# batteryBalancer.net
KiCad netlist of a schematic drawn in EAGLE
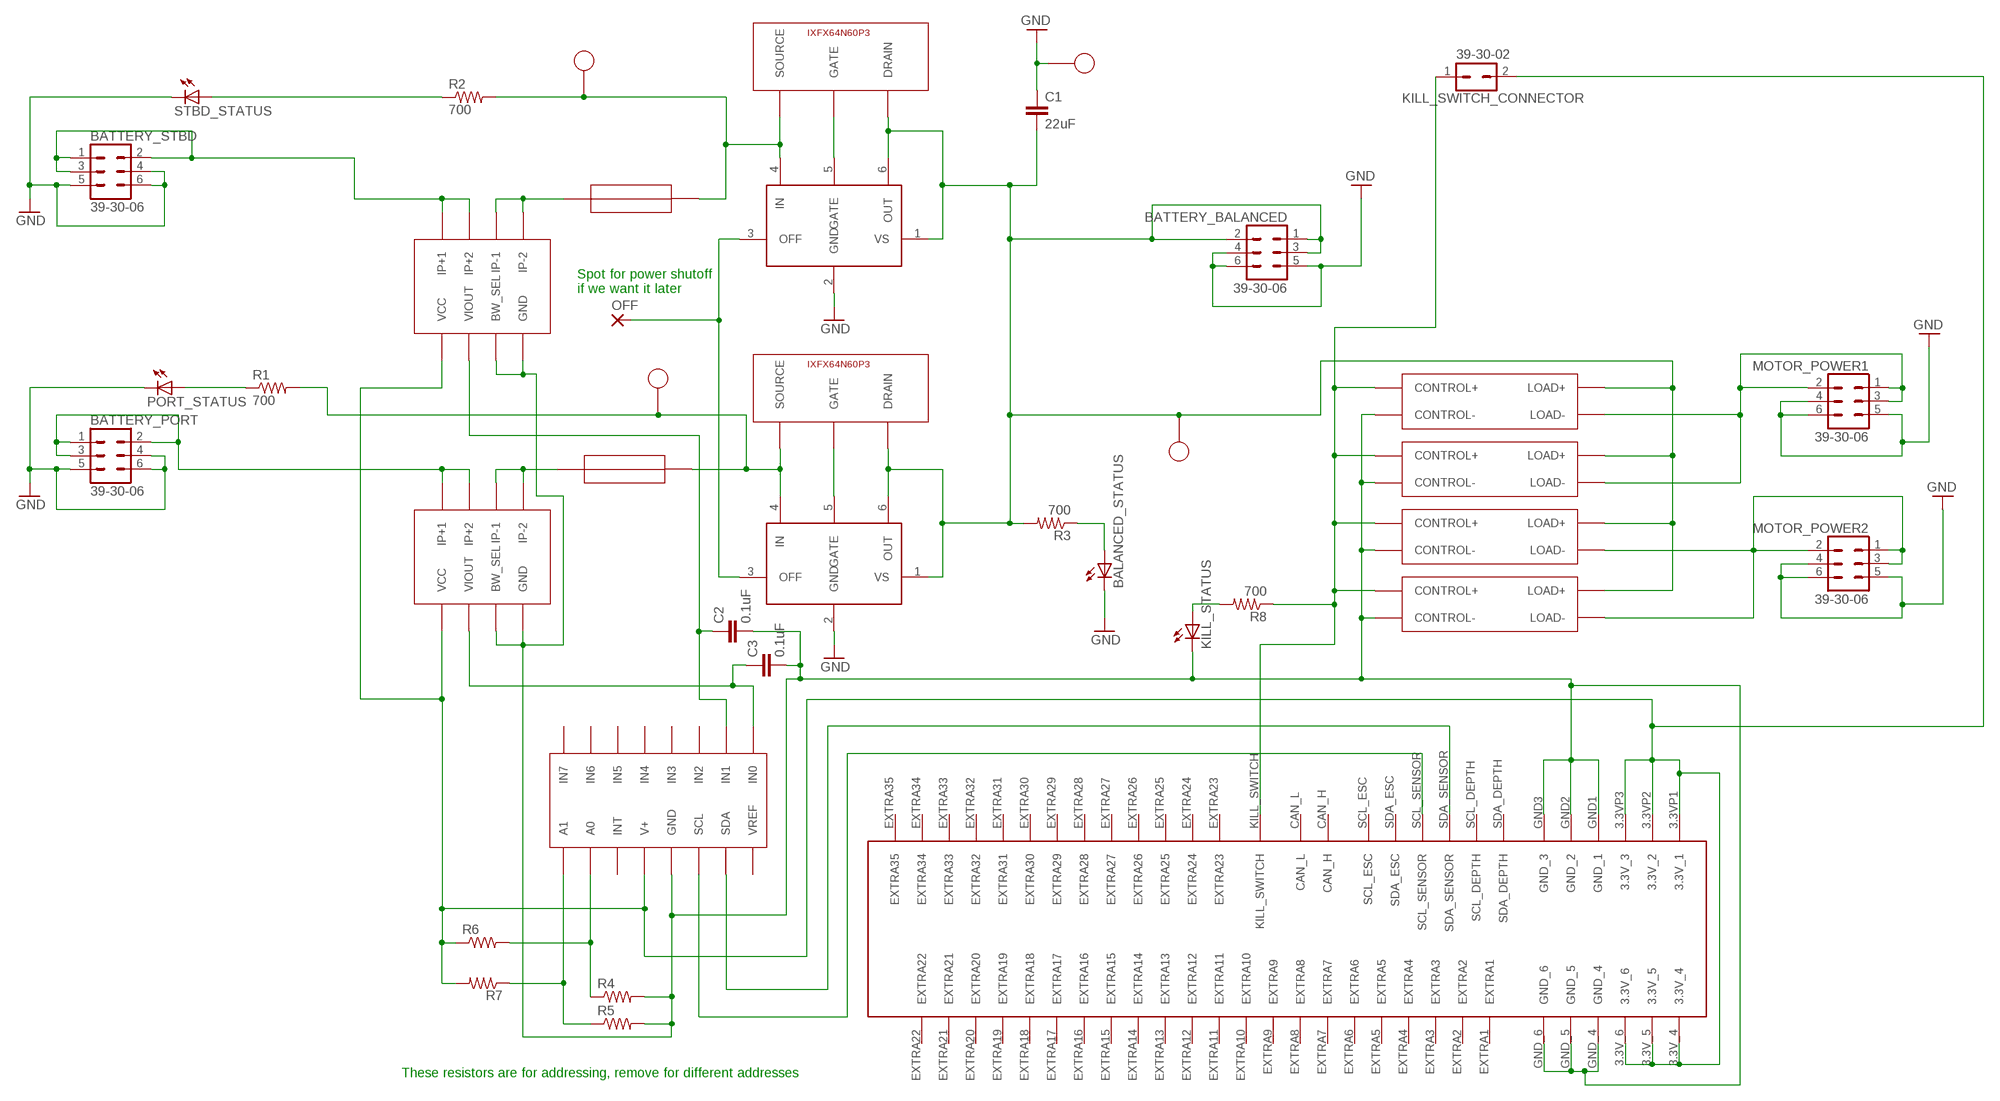
[diagram p0: schematic, sheet 1]

(export (version "E")
  (design (tool "Eeschema 10.0.6"))
  (components
    (comp (ref "ADC")
      (value "ADC128D818")
      (footprint "eagle-import:TSSOP-16")
      (libsource (lib "eagle-import") (part "ADC128D818"))
    )
    (comp (ref "BALANCED_STATUS")
      (value "LTST-S270GKT")
      (footprint "eagle-import:LTST-S270GKT")
      (libsource (lib "eagle-import") (part "LTST-S270GKT"))
    )
    (comp (ref "BATTERY_BALANCED")
      (value "39-30-06")
      (footprint "eagle-import:39-30-_06_")
      (libsource (lib "eagle-import") (part "39-30-?06?"))
    )
    (comp (ref "BATTERY_PORT")
      (value "39-30-06")
      (footprint "eagle-import:39-30-_06_")
      (libsource (lib "eagle-import") (part "39-30-?06?"))
    )
    (comp (ref "BATTERY_STBD")
      (value "39-30-06")
      (footprint "eagle-import:39-30-_06_")
      (libsource (lib "eagle-import") (part "39-30-?06?"))
    )
    (comp (ref "C1")
      (value "22uF")
      (footprint "eagle-import:CAP-PTH-SMALL-KIT")
      (libsource (lib "eagle-import") (part "0.1UF-KIT-EZ-50V-20%"))
    )
    (comp (ref "C2")
      (value "0.1uF")
      (footprint "eagle-import:CAP-PTH-SMALL-KIT")
      (libsource (lib "eagle-import") (part "0.1UF-KIT-EZ-50V-20%"))
    )
    (comp (ref "C3")
      (value "0.1uF")
      (footprint "eagle-import:CAP-PTH-SMALL-KIT")
      (libsource (lib "eagle-import") (part "0.1UF-KIT-EZ-50V-20%"))
    )
    (comp (ref "EDGE_CONNECTOR")
      (value "5530843")
      (footprint "eagle-import:5530843-6-BOARDFINGERS")
      (libsource (lib "eagle-import") (part "5530843"))
    )
    (comp (ref "KILL_STATUS")
      (value "LTST-S270GKT")
      (footprint "eagle-import:LTST-S270GKT")
      (libsource (lib "eagle-import") (part "LTST-S270GKT"))
    )
    (comp (ref "KILL_SWITCH_CONNECTOR")
      (value "39-30-02")
      (footprint "eagle-import:39-30-_02_")
      (libsource (lib "eagle-import") (part "39-30-?02?"))
    )
    (comp (ref "MOTOR_POWER1")
      (value "39-30-06")
      (footprint "eagle-import:39-30-_06_")
      (libsource (lib "eagle-import") (part "39-30-?06?"))
    )
    (comp (ref "MOTOR_POWER2")
      (value "39-30-06")
      (footprint "eagle-import:39-30-_06_")
      (libsource (lib "eagle-import") (part "39-30-?06?"))
    )
    (comp (ref "OFF")
      (value "2,54/1,1")
      (footprint "eagle-import:2,54_1,1")
      (libsource (lib "eagle-import") (part "2,54/1,1"))
    )
    (comp (ref "PORT_CS")
      (value "ACS722")
      (footprint "eagle-import:SOIC-8")
      (libsource (lib "eagle-import") (part "ACS722"))
    )
    (comp (ref "PORT_FC")
      (value "LM5050-1")
      (footprint "eagle-import:SOT23-6")
      (libsource (lib "eagle-import") (part "LM5050-1"))
    )
    (comp (ref "PORT_FET")
      (value "IXFX64N60P3")
      (footprint "eagle-import:IXFX64N60P3")
      (libsource (lib "eagle-import") (part "IXFX64N60P3"))
    )
    (comp (ref "PORT_FUSE")
      (value "01220083Z")
      (footprint "eagle-import:01220083Z")
      (libsource (lib "eagle-import") (part "01220083Z"))
    )
    (comp (ref "PORT_STATUS")
      (value "LTST-S270GKT")
      (footprint "eagle-import:LTST-S270GKT")
      (libsource (lib "eagle-import") (part "LTST-S270GKT"))
    )
    (comp (ref "R1")
      (value "700")
      (footprint "eagle-import:0207_7")
      (libsource (lib "eagle-import") (part "R-US_0207/7"))
    )
    (comp (ref "R2")
      (value "700")
      (footprint "eagle-import:0207_7")
      (libsource (lib "eagle-import") (part "R-US_0207/7"))
    )
    (comp (ref "R3")
      (value "700")
      (footprint "eagle-import:0207_7")
      (libsource (lib "eagle-import") (part "R-US_0207/7"))
    )
    (comp (ref "R4")
      (value "R-US_0204/5")
      (footprint "eagle-import:0204_5")
      (libsource (lib "eagle-import") (part "resistor_348_R-US_0204/5"))
    )
    (comp (ref "R5")
      (value "R-US_0204/5")
      (footprint "eagle-import:0204_5")
      (libsource (lib "eagle-import") (part "resistor_348_R-US_0204/5"))
    )
    (comp (ref "R6")
      (value "R-US_0204/5")
      (footprint "eagle-import:0204_5")
      (libsource (lib "eagle-import") (part "resistor_348_R-US_0204/5"))
    )
    (comp (ref "R7")
      (value "R-US_0204/5")
      (footprint "eagle-import:0204_5")
      (libsource (lib "eagle-import") (part "resistor_348_R-US_0204/5"))
    )
    (comp (ref "R8")
      (value "700")
      (footprint "eagle-import:0207_7")
      (libsource (lib "eagle-import") (part "R-US_0207/7"))
    )
    (comp (ref "RELAY2")
      (value "CMX60D20")
      (footprint "eagle-import:CMX60D20")
      (libsource (lib "eagle-import") (part "CMX60D20"))
    )
    (comp (ref "RELAY3")
      (value "CMX60D20")
      (footprint "eagle-import:CMX60D20")
      (libsource (lib "eagle-import") (part "CMX60D20"))
    )
    (comp (ref "RELAY4")
      (value "CMX60D20")
      (footprint "eagle-import:CMX60D20")
      (libsource (lib "eagle-import") (part "CMX60D20"))
    )
    (comp (ref "RLAY1")
      (value "CMX60D20")
      (footprint "eagle-import:CMX60D20")
      (libsource (lib "eagle-import") (part "CMX60D20"))
    )
    (comp (ref "STBD_CS")
      (value "ACS722")
      (footprint "eagle-import:SOIC-8")
      (libsource (lib "eagle-import") (part "ACS722"))
    )
    (comp (ref "STBD_FC")
      (value "LM5050-1")
      (footprint "eagle-import:SOT23-6")
      (libsource (lib "eagle-import") (part "LM5050-1"))
    )
    (comp (ref "STBD_FET")
      (value "IXFX64N60P3")
      (footprint "eagle-import:IXFX64N60P3")
      (libsource (lib "eagle-import") (part "IXFX64N60P3"))
    )
    (comp (ref "STBD_FUSE")
      (value "01220083Z")
      (footprint "eagle-import:01220083Z")
      (libsource (lib "eagle-import") (part "01220083Z"))
    )
    (comp (ref "STBD_STATUS")
      (value "LTST-S270GKT")
      (footprint "eagle-import:LTST-S270GKT")
      (libsource (lib "eagle-import") (part "LTST-S270GKT"))
    )
    (comp (ref "U$1")
      (value "5010_C")
      (footprint "eagle-import:5010_C")
      (libsource (lib "eagle-import") (part "5010_C"))
    )
    (comp (ref "U$2")
      (value "5010_C")
      (footprint "eagle-import:5010_C")
      (libsource (lib "eagle-import") (part "5010_C"))
    )
    (comp (ref "U$3")
      (value "5010_C")
      (footprint "eagle-import:5010_C")
      (libsource (lib "eagle-import") (part "5010_C"))
    )
    (comp (ref "U$4")
      (value "5010_C")
      (footprint "eagle-import:5010_C")
      (libsource (lib "eagle-import") (part "5010_C"))
    )
  )
  (nets
    (net (code "1") (name "GND") (class "Default")
      (node (ref "BALANCED_STATUS") (pin "CATHODE") (pinfunction "C_CATHODE") (pintype "passive"))
      (node (ref "BATTERY_BALANCED") (pin "4") (pinfunction "4_4") (pintype "passive"))
      (node (ref "BATTERY_BALANCED") (pin "5") (pinfunction "5_5") (pintype "passive"))
      (node (ref "BATTERY_BALANCED") (pin "6") (pinfunction "6_6") (pintype "passive"))
      (node (ref "BATTERY_PORT") (pin "4") (pinfunction "4_4") (pintype "passive"))
      (node (ref "BATTERY_PORT") (pin "5") (pinfunction "5_5") (pintype "passive"))
      (node (ref "BATTERY_PORT") (pin "6") (pinfunction "6_6") (pintype "passive"))
      (node (ref "BATTERY_STBD") (pin "4") (pinfunction "4_4") (pintype "passive"))
      (node (ref "BATTERY_STBD") (pin "5") (pinfunction "5_5") (pintype "passive"))
      (node (ref "BATTERY_STBD") (pin "6") (pinfunction "6_6") (pintype "passive"))
      (node (ref "C1") (pin "1") (pinfunction "1_1") (pintype "passive"))
      (node (ref "MOTOR_POWER1") (pin "4") (pinfunction "4_4") (pintype "passive"))
      (node (ref "MOTOR_POWER1") (pin "5") (pinfunction "5_5") (pintype "passive"))
      (node (ref "MOTOR_POWER1") (pin "6") (pinfunction "6_6") (pintype "passive"))
      (node (ref "MOTOR_POWER2") (pin "4") (pinfunction "4_4") (pintype "passive"))
      (node (ref "MOTOR_POWER2") (pin "5") (pinfunction "5_5") (pintype "passive"))
      (node (ref "MOTOR_POWER2") (pin "6") (pinfunction "6_6") (pintype "passive"))
      (node (ref "PORT_FC") (pin "2") (pinfunction "GND_2") (pintype "bidirectional"))
      (node (ref "PORT_STATUS") (pin "CATHODE") (pinfunction "C_CATHODE") (pintype "passive"))
      (node (ref "STBD_FC") (pin "2") (pinfunction "GND_2") (pintype "bidirectional"))
      (node (ref "STBD_STATUS") (pin "CATHODE") (pinfunction "C_CATHODE") (pintype "passive"))
      (node (ref "U$4") (pin "P$1") (pinfunction "P$1_P$1") (pintype "bidirectional"))
    )
    (net (code "2") (name "Net-(ADC-PadA0)") (class "Default")
      (node (ref "ADC") (pin "A0") (pinfunction "A0_A0") (pintype "bidirectional"))
      (node (ref "R4") (pin "1") (pinfunction "1_1") (pintype "passive"))
      (node (ref "R6") (pin "2") (pinfunction "2_2") (pintype "passive"))
    )
    (net (code "3") (name "Net-(ADC-PadA1)") (class "Default")
      (node (ref "ADC") (pin "A1") (pinfunction "A1_A1") (pintype "bidirectional"))
      (node (ref "R5") (pin "1") (pinfunction "1_1") (pintype "passive"))
      (node (ref "R7") (pin "1") (pinfunction "1_1") (pintype "passive"))
    )
    (net (code "4") (name "Net-(ADC-PadIN0)") (class "Default")
      (node (ref "ADC") (pin "IN0") (pinfunction "IN0_IN0") (pintype "bidirectional"))
      (node (ref "C3") (pin "1") (pinfunction "1_1") (pintype "passive"))
      (node (ref "PORT_CS") (pin "VIOUT") (pinfunction "VIOUT_VIOUT") (pintype "bidirectional"))
    )
    (net (code "5") (name "Net-(ADC-PadIN1)") (class "Default")
      (node (ref "ADC") (pin "IN1") (pinfunction "IN1_IN1") (pintype "bidirectional"))
      (node (ref "C2") (pin "1") (pinfunction "1_1") (pintype "passive"))
      (node (ref "STBD_CS") (pin "VIOUT") (pinfunction "VIOUT_VIOUT") (pintype "bidirectional"))
    )
    (net (code "6") (name "Net-(ADC-PadSCL)") (class "Default")
      (node (ref "ADC") (pin "SCL") (pinfunction "SCL_SCL") (pintype "bidirectional"))
      (node (ref "EDGE_CONNECTOR") (pin "SCL_SENSOR") (pinfunction "SCL_SENSOR_SCL_SENSOR") (pintype "bidirectional"))
    )
    (net (code "7") (name "Net-(ADC-PadSDA)") (class "Default")
      (node (ref "ADC") (pin "SDA") (pinfunction "SDA_SDA") (pintype "bidirectional"))
      (node (ref "EDGE_CONNECTOR") (pin "SDA_SENSOR") (pinfunction "SDA_SENSOR_SDA_SENSOR") (pintype "bidirectional"))
    )
    (net (code "8") (name "Net-(BALANCED_STATUS-A)") (class "Default")
      (node (ref "BALANCED_STATUS") (pin "ANODE") (pinfunction "A_ANODE") (pintype "passive"))
      (node (ref "R3") (pin "1") (pinfunction "1_1") (pintype "passive"))
    )
    (net (code "9") (name "Net-(BATTERY_PORT-Pad1)") (class "Default")
      (node (ref "BATTERY_PORT") (pin "1") (pinfunction "1_1") (pintype "passive"))
      (node (ref "BATTERY_PORT") (pin "2") (pinfunction "2_2") (pintype "passive"))
      (node (ref "BATTERY_PORT") (pin "3") (pinfunction "3_3") (pintype "passive"))
      (node (ref "PORT_CS") (pin "IP+1") (pinfunction "IP+1_IP+1") (pintype "bidirectional"))
      (node (ref "PORT_CS") (pin "IP+2") (pinfunction "IP+2_IP+2") (pintype "bidirectional"))
    )
    (net (code "10") (name "Net-(BATTERY_STBD-Pad1)") (class "Default")
      (node (ref "BATTERY_STBD") (pin "1") (pinfunction "1_1") (pintype "passive"))
      (node (ref "BATTERY_STBD") (pin "2") (pinfunction "2_2") (pintype "passive"))
      (node (ref "BATTERY_STBD") (pin "3") (pinfunction "3_3") (pintype "passive"))
      (node (ref "STBD_CS") (pin "IP+1") (pinfunction "IP+1_IP+1") (pintype "bidirectional"))
      (node (ref "STBD_CS") (pin "IP+2") (pinfunction "IP+2_IP+2") (pintype "bidirectional"))
    )
    (net (code "11") (name "Net-(EDGE_CONNECTOR-3.3V_1)") (class "Default")
      (node (ref "ADC") (pin "V+") (pinfunction "V+_V+") (pintype "bidirectional"))
      (node (ref "EDGE_CONNECTOR") (pin "3.3VP1") (pinfunction "3.3V_1_3.3VP1") (pintype "bidirectional"))
      (node (ref "EDGE_CONNECTOR") (pin "3.3VP2") (pinfunction "3.3V_2_3.3VP2") (pintype "bidirectional"))
      (node (ref "EDGE_CONNECTOR") (pin "3.3VP3") (pinfunction "3.3V_3_3.3VP3") (pintype "bidirectional"))
      (node (ref "EDGE_CONNECTOR") (pin "3.3V_4") (pinfunction "3.3V_4_3.3V_4") (pintype "bidirectional"))
      (node (ref "EDGE_CONNECTOR") (pin "3.3V_5") (pinfunction "3.3V_5_3.3V_5") (pintype "bidirectional"))
      (node (ref "EDGE_CONNECTOR") (pin "3.3V_6") (pinfunction "3.3V_6_3.3V_6") (pintype "bidirectional"))
      (node (ref "KILL_SWITCH_CONNECTOR") (pin "2") (pinfunction "2_2") (pintype "passive"))
      (node (ref "PORT_CS") (pin "VCC") (pinfunction "VCC_VCC") (pintype "bidirectional"))
      (node (ref "R6") (pin "1") (pinfunction "1_1") (pintype "passive"))
      (node (ref "R7") (pin "2") (pinfunction "2_2") (pintype "passive"))
      (node (ref "STBD_CS") (pin "VCC") (pinfunction "VCC_VCC") (pintype "bidirectional"))
    )
    (net (code "12") (name "Net-(EDGE_CONNECTOR-GND_1)") (class "Default")
      (node (ref "ADC") (pin "GND") (pinfunction "GND_GND") (pintype "bidirectional"))
      (node (ref "C2") (pin "2") (pinfunction "2_2") (pintype "passive"))
      (node (ref "C3") (pin "2") (pinfunction "2_2") (pintype "passive"))
      (node (ref "EDGE_CONNECTOR") (pin "GND1") (pinfunction "GND_1_GND1") (pintype "bidirectional"))
      (node (ref "EDGE_CONNECTOR") (pin "GND2") (pinfunction "GND_2_GND2") (pintype "bidirectional"))
      (node (ref "EDGE_CONNECTOR") (pin "GND3") (pinfunction "GND_3_GND3") (pintype "bidirectional"))
      (node (ref "EDGE_CONNECTOR") (pin "GND_4") (pinfunction "GND_4_GND_4") (pintype "bidirectional"))
      (node (ref "EDGE_CONNECTOR") (pin "GND_5") (pinfunction "GND_5_GND_5") (pintype "bidirectional"))
      (node (ref "EDGE_CONNECTOR") (pin "GND_6") (pinfunction "GND_6_GND_6") (pintype "bidirectional"))
      (node (ref "KILL_STATUS") (pin "CATHODE") (pinfunction "C_CATHODE") (pintype "passive"))
      (node (ref "PORT_CS") (pin "BW_SEL") (pinfunction "BW_SEL_BW_SEL") (pintype "bidirectional"))
      (node (ref "PORT_CS") (pin "GND") (pinfunction "GND_GND") (pintype "bidirectional"))
      (node (ref "R4") (pin "2") (pinfunction "2_2") (pintype "passive"))
      (node (ref "R5") (pin "2") (pinfunction "2_2") (pintype "passive"))
      (node (ref "RELAY2") (pin "CONTROL-") (pinfunction "CONTROL-_CONTROL-") (pintype "bidirectional"))
      (node (ref "RELAY3") (pin "CONTROL-") (pinfunction "CONTROL-_CONTROL-") (pintype "bidirectional"))
      (node (ref "RELAY4") (pin "CONTROL-") (pinfunction "CONTROL-_CONTROL-") (pintype "bidirectional"))
      (node (ref "RLAY1") (pin "CONTROL-") (pinfunction "CONTROL-_CONTROL-") (pintype "bidirectional"))
      (node (ref "STBD_CS") (pin "BW_SEL") (pinfunction "BW_SEL_BW_SEL") (pintype "bidirectional"))
      (node (ref "STBD_CS") (pin "GND") (pinfunction "GND_GND") (pintype "bidirectional"))
    )
    (net (code "13") (name "Net-(EDGE_CONNECTOR-PadKILL_SWITCH)") (class "Default")
      (node (ref "EDGE_CONNECTOR") (pin "KILL_SWITCH") (pinfunction "KILL_SWITCH_KILL_SWITCH") (pintype "bidirectional"))
      (node (ref "KILL_SWITCH_CONNECTOR") (pin "1") (pinfunction "1_1") (pintype "passive"))
      (node (ref "R8") (pin "1") (pinfunction "1_1") (pintype "passive"))
      (node (ref "RELAY2") (pin "CONTROL+") (pinfunction "CONTROL+_CONTROL+") (pintype "bidirectional"))
      (node (ref "RELAY3") (pin "CONTROL+") (pinfunction "CONTROL+_CONTROL+") (pintype "bidirectional"))
      (node (ref "RELAY4") (pin "CONTROL+") (pinfunction "CONTROL+_CONTROL+") (pintype "bidirectional"))
      (node (ref "RLAY1") (pin "CONTROL+") (pinfunction "CONTROL+_CONTROL+") (pintype "bidirectional"))
    )
    (net (code "14") (name "Net-(KILL_STATUS-A)") (class "Default")
      (node (ref "KILL_STATUS") (pin "ANODE") (pinfunction "A_ANODE") (pintype "passive"))
      (node (ref "R8") (pin "2") (pinfunction "2_2") (pintype "passive"))
    )
    (net (code "15") (name "Net-(MOTOR_POWER1-Pad1)") (class "Default")
      (node (ref "MOTOR_POWER1") (pin "1") (pinfunction "1_1") (pintype "passive"))
      (node (ref "MOTOR_POWER1") (pin "2") (pinfunction "2_2") (pintype "passive"))
      (node (ref "MOTOR_POWER1") (pin "3") (pinfunction "3_3") (pintype "passive"))
      (node (ref "RELAY2") (pin "LOAD-") (pinfunction "LOAD-_LOAD-") (pintype "bidirectional"))
      (node (ref "RLAY1") (pin "LOAD-") (pinfunction "LOAD-_LOAD-") (pintype "bidirectional"))
    )
    (net (code "16") (name "Net-(MOTOR_POWER2-Pad1)") (class "Default")
      (node (ref "MOTOR_POWER2") (pin "1") (pinfunction "1_1") (pintype "passive"))
      (node (ref "MOTOR_POWER2") (pin "2") (pinfunction "2_2") (pintype "passive"))
      (node (ref "MOTOR_POWER2") (pin "3") (pinfunction "3_3") (pintype "passive"))
      (node (ref "RELAY3") (pin "LOAD-") (pinfunction "LOAD-_LOAD-") (pintype "bidirectional"))
      (node (ref "RELAY4") (pin "LOAD-") (pinfunction "LOAD-_LOAD-") (pintype "bidirectional"))
    )
    (net (code "17") (name "Net-(OFF-P)") (class "Default")
      (node (ref "OFF") (pin "1") (pinfunction "P_1") (pintype "passive"))
      (node (ref "PORT_FC") (pin "3") (pinfunction "OFF_3") (pintype "bidirectional"))
      (node (ref "STBD_FC") (pin "3") (pinfunction "OFF_3") (pintype "bidirectional"))
    )
    (net (code "18") (name "Net-(PORT_CS-PadIP-1)") (class "Default")
      (node (ref "PORT_CS") (pin "IP-1") (pinfunction "IP-1_IP-1") (pintype "bidirectional"))
      (node (ref "PORT_CS") (pin "IP-2") (pinfunction "IP-2_IP-2") (pintype "bidirectional"))
      (node (ref "PORT_FUSE") (pin "P$1") (pinfunction "P$1_P$1") (pintype "bidirectional"))
      (node (ref "PORT_FUSE") (pin "P$2") (pinfunction "P$1_P$2") (pintype "bidirectional"))
    )
    (net (code "19") (name "Net-(PORT_FC-GATE)") (class "Default")
      (node (ref "PORT_FC") (pin "5") (pinfunction "GATE_5") (pintype "bidirectional"))
      (node (ref "PORT_FET") (pin "GATE") (pinfunction "GATE_GATE") (pintype "bidirectional"))
    )
    (net (code "20") (name "Net-(PORT_FC-IN)") (class "Default")
      (node (ref "PORT_FC") (pin "4") (pinfunction "IN_4") (pintype "bidirectional"))
      (node (ref "PORT_FET") (pin "SOURCE") (pinfunction "SOURCE_SOURCE") (pintype "bidirectional"))
      (node (ref "PORT_FUSE") (pin "P$3") (pinfunction "P$2_P$3") (pintype "bidirectional"))
      (node (ref "PORT_FUSE") (pin "P$4") (pinfunction "P$2_P$4") (pintype "bidirectional"))
      (node (ref "R1") (pin "2") (pinfunction "2_2") (pintype "passive"))
      (node (ref "U$2") (pin "P$1") (pinfunction "P$1_P$1") (pintype "bidirectional"))
    )
    (net (code "21") (name "Net-(PORT_FC-OUT)") (class "Default")
      (node (ref "BATTERY_BALANCED") (pin "1") (pinfunction "1_1") (pintype "passive"))
      (node (ref "BATTERY_BALANCED") (pin "2") (pinfunction "2_2") (pintype "passive"))
      (node (ref "BATTERY_BALANCED") (pin "3") (pinfunction "3_3") (pintype "passive"))
      (node (ref "C1") (pin "2") (pinfunction "2_2") (pintype "passive"))
      (node (ref "PORT_FC") (pin "1") (pinfunction "VS_1") (pintype "bidirectional"))
      (node (ref "PORT_FC") (pin "6") (pinfunction "OUT_6") (pintype "bidirectional"))
      (node (ref "PORT_FET") (pin "DRAIN") (pinfunction "DRAIN_DRAIN") (pintype "bidirectional"))
      (node (ref "R3") (pin "2") (pinfunction "2_2") (pintype "passive"))
      (node (ref "RELAY2") (pin "LOAD+") (pinfunction "LOAD+_LOAD+") (pintype "bidirectional"))
      (node (ref "RELAY3") (pin "LOAD+") (pinfunction "LOAD+_LOAD+") (pintype "bidirectional"))
      (node (ref "RELAY4") (pin "LOAD+") (pinfunction "LOAD+_LOAD+") (pintype "bidirectional"))
      (node (ref "RLAY1") (pin "LOAD+") (pinfunction "LOAD+_LOAD+") (pintype "bidirectional"))
      (node (ref "STBD_FC") (pin "1") (pinfunction "VS_1") (pintype "bidirectional"))
      (node (ref "STBD_FC") (pin "6") (pinfunction "OUT_6") (pintype "bidirectional"))
      (node (ref "STBD_FET") (pin "DRAIN") (pinfunction "DRAIN_DRAIN") (pintype "bidirectional"))
      (node (ref "U$3") (pin "P$1") (pinfunction "P$1_P$1") (pintype "bidirectional"))
    )
    (net (code "22") (name "Net-(PORT_STATUS-A)") (class "Default")
      (node (ref "PORT_STATUS") (pin "ANODE") (pinfunction "A_ANODE") (pintype "passive"))
      (node (ref "R1") (pin "1") (pinfunction "1_1") (pintype "passive"))
    )
    (net (code "23") (name "Net-(STBD_CS-PadIP-1)") (class "Default")
      (node (ref "STBD_CS") (pin "IP-1") (pinfunction "IP-1_IP-1") (pintype "bidirectional"))
      (node (ref "STBD_CS") (pin "IP-2") (pinfunction "IP-2_IP-2") (pintype "bidirectional"))
      (node (ref "STBD_FUSE") (pin "P$1") (pinfunction "P$1_P$1") (pintype "bidirectional"))
      (node (ref "STBD_FUSE") (pin "P$2") (pinfunction "P$1_P$2") (pintype "bidirectional"))
    )
    (net (code "24") (name "Net-(STBD_FC-GATE)") (class "Default")
      (node (ref "STBD_FC") (pin "5") (pinfunction "GATE_5") (pintype "bidirectional"))
      (node (ref "STBD_FET") (pin "GATE") (pinfunction "GATE_GATE") (pintype "bidirectional"))
    )
    (net (code "25") (name "Net-(STBD_FC-IN)") (class "Default")
      (node (ref "R2") (pin "2") (pinfunction "2_2") (pintype "passive"))
      (node (ref "STBD_FC") (pin "4") (pinfunction "IN_4") (pintype "bidirectional"))
      (node (ref "STBD_FET") (pin "SOURCE") (pinfunction "SOURCE_SOURCE") (pintype "bidirectional"))
      (node (ref "STBD_FUSE") (pin "P$3") (pinfunction "P$2_P$3") (pintype "bidirectional"))
      (node (ref "STBD_FUSE") (pin "P$4") (pinfunction "P$2_P$4") (pintype "bidirectional"))
      (node (ref "U$1") (pin "P$1") (pinfunction "P$1_P$1") (pintype "bidirectional"))
    )
    (net (code "26") (name "Net-(STBD_STATUS-A)") (class "Default")
      (node (ref "R2") (pin "1") (pinfunction "1_1") (pintype "passive"))
      (node (ref "STBD_STATUS") (pin "ANODE") (pinfunction "A_ANODE") (pintype "passive"))
    )
    (net (code "27") (name "unconnected-(ADC-PadIN2)") (class "Default")
      (node (ref "ADC") (pin "IN2") (pinfunction "IN2_IN2") (pintype "bidirectional"))
    )
    (net (code "28") (name "unconnected-(ADC-PadIN3)") (class "Default")
      (node (ref "ADC") (pin "IN3") (pinfunction "IN3_IN3") (pintype "bidirectional"))
    )
    (net (code "29") (name "unconnected-(ADC-PadIN4)") (class "Default")
      (node (ref "ADC") (pin "IN4") (pinfunction "IN4_IN4") (pintype "bidirectional"))
    )
    (net (code "30") (name "unconnected-(ADC-PadIN5)") (class "Default")
      (node (ref "ADC") (pin "IN5") (pinfunction "IN5_IN5") (pintype "bidirectional"))
    )
    (net (code "31") (name "unconnected-(ADC-PadIN6)") (class "Default")
      (node (ref "ADC") (pin "IN6") (pinfunction "IN6_IN6") (pintype "bidirectional"))
    )
    (net (code "32") (name "unconnected-(ADC-PadIN7)") (class "Default")
      (node (ref "ADC") (pin "IN7") (pinfunction "IN7_IN7") (pintype "bidirectional"))
    )
    (net (code "33") (name "unconnected-(ADC-PadINT)") (class "Default")
      (node (ref "ADC") (pin "INT") (pinfunction "INT_INT") (pintype "bidirectional"))
    )
    (net (code "34") (name "unconnected-(ADC-PadVREF)") (class "Default")
      (node (ref "ADC") (pin "VREF") (pinfunction "VREF_VREF") (pintype "bidirectional"))
    )
    (net (code "35") (name "unconnected-(EDGE_CONNECTOR-PadCAN_H)") (class "Default")
      (node (ref "EDGE_CONNECTOR") (pin "CAN_H") (pinfunction "CAN_H_CAN_H") (pintype "bidirectional"))
    )
    (net (code "36") (name "unconnected-(EDGE_CONNECTOR-PadCAN_L)") (class "Default")
      (node (ref "EDGE_CONNECTOR") (pin "CAN_L") (pinfunction "CAN_L_CAN_L") (pintype "bidirectional"))
    )
    (net (code "37") (name "unconnected-(EDGE_CONNECTOR-PadEXTRA1)") (class "Default")
      (node (ref "EDGE_CONNECTOR") (pin "EXTRA1") (pinfunction "EXTRA1_EXTRA1") (pintype "bidirectional"))
    )
    (net (code "38") (name "unconnected-(EDGE_CONNECTOR-PadEXTRA2)") (class "Default")
      (node (ref "EDGE_CONNECTOR") (pin "EXTRA2") (pinfunction "EXTRA2_EXTRA2") (pintype "bidirectional"))
    )
    (net (code "39") (name "unconnected-(EDGE_CONNECTOR-PadEXTRA3)") (class "Default")
      (node (ref "EDGE_CONNECTOR") (pin "EXTRA3") (pinfunction "EXTRA3_EXTRA3") (pintype "bidirectional"))
    )
    (net (code "40") (name "unconnected-(EDGE_CONNECTOR-PadEXTRA4)") (class "Default")
      (node (ref "EDGE_CONNECTOR") (pin "EXTRA4") (pinfunction "EXTRA4_EXTRA4") (pintype "bidirectional"))
    )
    (net (code "41") (name "unconnected-(EDGE_CONNECTOR-PadEXTRA5)") (class "Default")
      (node (ref "EDGE_CONNECTOR") (pin "EXTRA5") (pinfunction "EXTRA5_EXTRA5") (pintype "bidirectional"))
    )
    (net (code "42") (name "unconnected-(EDGE_CONNECTOR-PadEXTRA6)") (class "Default")
      (node (ref "EDGE_CONNECTOR") (pin "EXTRA6") (pinfunction "EXTRA6_EXTRA6") (pintype "bidirectional"))
    )
    (net (code "43") (name "unconnected-(EDGE_CONNECTOR-PadEXTRA7)") (class "Default")
      (node (ref "EDGE_CONNECTOR") (pin "EXTRA7") (pinfunction "EXTRA7_EXTRA7") (pintype "bidirectional"))
    )
    (net (code "44") (name "unconnected-(EDGE_CONNECTOR-PadEXTRA8)") (class "Default")
      (node (ref "EDGE_CONNECTOR") (pin "EXTRA8") (pinfunction "EXTRA8_EXTRA8") (pintype "bidirectional"))
    )
    (net (code "45") (name "unconnected-(EDGE_CONNECTOR-PadEXTRA9)") (class "Default")
      (node (ref "EDGE_CONNECTOR") (pin "EXTRA9") (pinfunction "EXTRA9_EXTRA9") (pintype "bidirectional"))
    )
    (net (code "46") (name "unconnected-(EDGE_CONNECTOR-PadEXTRA10)") (class "Default")
      (node (ref "EDGE_CONNECTOR") (pin "EXTRA10") (pinfunction "EXTRA10_EXTRA10") (pintype "bidirectional"))
    )
    (net (code "47") (name "unconnected-(EDGE_CONNECTOR-PadEXTRA11)") (class "Default")
      (node (ref "EDGE_CONNECTOR") (pin "EXTRA11") (pinfunction "EXTRA11_EXTRA11") (pintype "bidirectional"))
    )
    (net (code "48") (name "unconnected-(EDGE_CONNECTOR-PadEXTRA12)") (class "Default")
      (node (ref "EDGE_CONNECTOR") (pin "EXTRA12") (pinfunction "EXTRA12_EXTRA12") (pintype "bidirectional"))
    )
    (net (code "49") (name "unconnected-(EDGE_CONNECTOR-PadEXTRA13)") (class "Default")
      (node (ref "EDGE_CONNECTOR") (pin "EXTRA13") (pinfunction "EXTRA13_EXTRA13") (pintype "bidirectional"))
    )
    (net (code "50") (name "unconnected-(EDGE_CONNECTOR-PadEXTRA14)") (class "Default")
      (node (ref "EDGE_CONNECTOR") (pin "EXTRA14") (pinfunction "EXTRA14_EXTRA14") (pintype "bidirectional"))
    )
    (net (code "51") (name "unconnected-(EDGE_CONNECTOR-PadEXTRA15)") (class "Default")
      (node (ref "EDGE_CONNECTOR") (pin "EXTRA15") (pinfunction "EXTRA15_EXTRA15") (pintype "bidirectional"))
    )
    (net (code "52") (name "unconnected-(EDGE_CONNECTOR-PadEXTRA16)") (class "Default")
      (node (ref "EDGE_CONNECTOR") (pin "EXTRA16") (pinfunction "EXTRA16_EXTRA16") (pintype "bidirectional"))
    )
    (net (code "53") (name "unconnected-(EDGE_CONNECTOR-PadEXTRA17)") (class "Default")
      (node (ref "EDGE_CONNECTOR") (pin "EXTRA17") (pinfunction "EXTRA17_EXTRA17") (pintype "bidirectional"))
    )
    (net (code "54") (name "unconnected-(EDGE_CONNECTOR-PadEXTRA18)") (class "Default")
      (node (ref "EDGE_CONNECTOR") (pin "EXTRA18") (pinfunction "EXTRA18_EXTRA18") (pintype "bidirectional"))
    )
    (net (code "55") (name "unconnected-(EDGE_CONNECTOR-PadEXTRA19)") (class "Default")
      (node (ref "EDGE_CONNECTOR") (pin "EXTRA19") (pinfunction "EXTRA19_EXTRA19") (pintype "bidirectional"))
    )
    (net (code "56") (name "unconnected-(EDGE_CONNECTOR-PadEXTRA20)") (class "Default")
      (node (ref "EDGE_CONNECTOR") (pin "EXTRA20") (pinfunction "EXTRA20_EXTRA20") (pintype "bidirectional"))
    )
    (net (code "57") (name "unconnected-(EDGE_CONNECTOR-PadEXTRA21)") (class "Default")
      (node (ref "EDGE_CONNECTOR") (pin "EXTRA21") (pinfunction "EXTRA21_EXTRA21") (pintype "bidirectional"))
    )
    (net (code "58") (name "unconnected-(EDGE_CONNECTOR-PadEXTRA22)") (class "Default")
      (node (ref "EDGE_CONNECTOR") (pin "EXTRA22") (pinfunction "EXTRA22_EXTRA22") (pintype "bidirectional"))
    )
    (net (code "59") (name "unconnected-(EDGE_CONNECTOR-PadEXTRA23)") (class "Default")
      (node (ref "EDGE_CONNECTOR") (pin "EXTRA23") (pinfunction "EXTRA23_EXTRA23") (pintype "bidirectional"))
    )
    (net (code "60") (name "unconnected-(EDGE_CONNECTOR-PadEXTRA24)") (class "Default")
      (node (ref "EDGE_CONNECTOR") (pin "EXTRA24") (pinfunction "EXTRA24_EXTRA24") (pintype "bidirectional"))
    )
    (net (code "61") (name "unconnected-(EDGE_CONNECTOR-PadEXTRA25)") (class "Default")
      (node (ref "EDGE_CONNECTOR") (pin "EXTRA25") (pinfunction "EXTRA25_EXTRA25") (pintype "bidirectional"))
    )
    (net (code "62") (name "unconnected-(EDGE_CONNECTOR-PadEXTRA26)") (class "Default")
      (node (ref "EDGE_CONNECTOR") (pin "EXTRA26") (pinfunction "EXTRA26_EXTRA26") (pintype "bidirectional"))
    )
    (net (code "63") (name "unconnected-(EDGE_CONNECTOR-PadEXTRA27)") (class "Default")
      (node (ref "EDGE_CONNECTOR") (pin "EXTRA27") (pinfunction "EXTRA27_EXTRA27") (pintype "bidirectional"))
    )
    (net (code "64") (name "unconnected-(EDGE_CONNECTOR-PadEXTRA28)") (class "Default")
      (node (ref "EDGE_CONNECTOR") (pin "EXTRA28") (pinfunction "EXTRA28_EXTRA28") (pintype "bidirectional"))
    )
    (net (code "65") (name "unconnected-(EDGE_CONNECTOR-PadEXTRA29)") (class "Default")
      (node (ref "EDGE_CONNECTOR") (pin "EXTRA29") (pinfunction "EXTRA29_EXTRA29") (pintype "bidirectional"))
    )
    (net (code "66") (name "unconnected-(EDGE_CONNECTOR-PadEXTRA30)") (class "Default")
      (node (ref "EDGE_CONNECTOR") (pin "EXTRA30") (pinfunction "EXTRA30_EXTRA30") (pintype "bidirectional"))
    )
    (net (code "67") (name "unconnected-(EDGE_CONNECTOR-PadEXTRA31)") (class "Default")
      (node (ref "EDGE_CONNECTOR") (pin "EXTRA31") (pinfunction "EXTRA31_EXTRA31") (pintype "bidirectional"))
    )
    (net (code "68") (name "unconnected-(EDGE_CONNECTOR-PadEXTRA32)") (class "Default")
      (node (ref "EDGE_CONNECTOR") (pin "EXTRA32") (pinfunction "EXTRA32_EXTRA32") (pintype "bidirectional"))
    )
    (net (code "69") (name "unconnected-(EDGE_CONNECTOR-PadEXTRA33)") (class "Default")
      (node (ref "EDGE_CONNECTOR") (pin "EXTRA33") (pinfunction "EXTRA33_EXTRA33") (pintype "bidirectional"))
    )
    (net (code "70") (name "unconnected-(EDGE_CONNECTOR-PadEXTRA34)") (class "Default")
      (node (ref "EDGE_CONNECTOR") (pin "EXTRA34") (pinfunction "EXTRA34_EXTRA34") (pintype "bidirectional"))
    )
    (net (code "71") (name "unconnected-(EDGE_CONNECTOR-PadEXTRA35)") (class "Default")
      (node (ref "EDGE_CONNECTOR") (pin "EXTRA35") (pinfunction "EXTRA35_EXTRA35") (pintype "bidirectional"))
    )
    (net (code "72") (name "unconnected-(EDGE_CONNECTOR-PadSCL_DEPTH)") (class "Default")
      (node (ref "EDGE_CONNECTOR") (pin "SCL_DEPTH") (pinfunction "SCL_DEPTH_SCL_DEPTH") (pintype "bidirectional"))
    )
    (net (code "73") (name "unconnected-(EDGE_CONNECTOR-PadSCL_ESC)") (class "Default")
      (node (ref "EDGE_CONNECTOR") (pin "SCL_ESC") (pinfunction "SCL_ESC_SCL_ESC") (pintype "bidirectional"))
    )
    (net (code "74") (name "unconnected-(EDGE_CONNECTOR-PadSDA_DEPTH)") (class "Default")
      (node (ref "EDGE_CONNECTOR") (pin "SDA_DEPTH") (pinfunction "SDA_DEPTH_SDA_DEPTH") (pintype "bidirectional"))
    )
    (net (code "75") (name "unconnected-(EDGE_CONNECTOR-PadSDA_ESC)") (class "Default")
      (node (ref "EDGE_CONNECTOR") (pin "SDA_ESC") (pinfunction "SDA_ESC_SDA_ESC") (pintype "bidirectional"))
    )
  )
)
